# 190812-1a.net
KiCad netlist of a schematic drawn in EAGLE
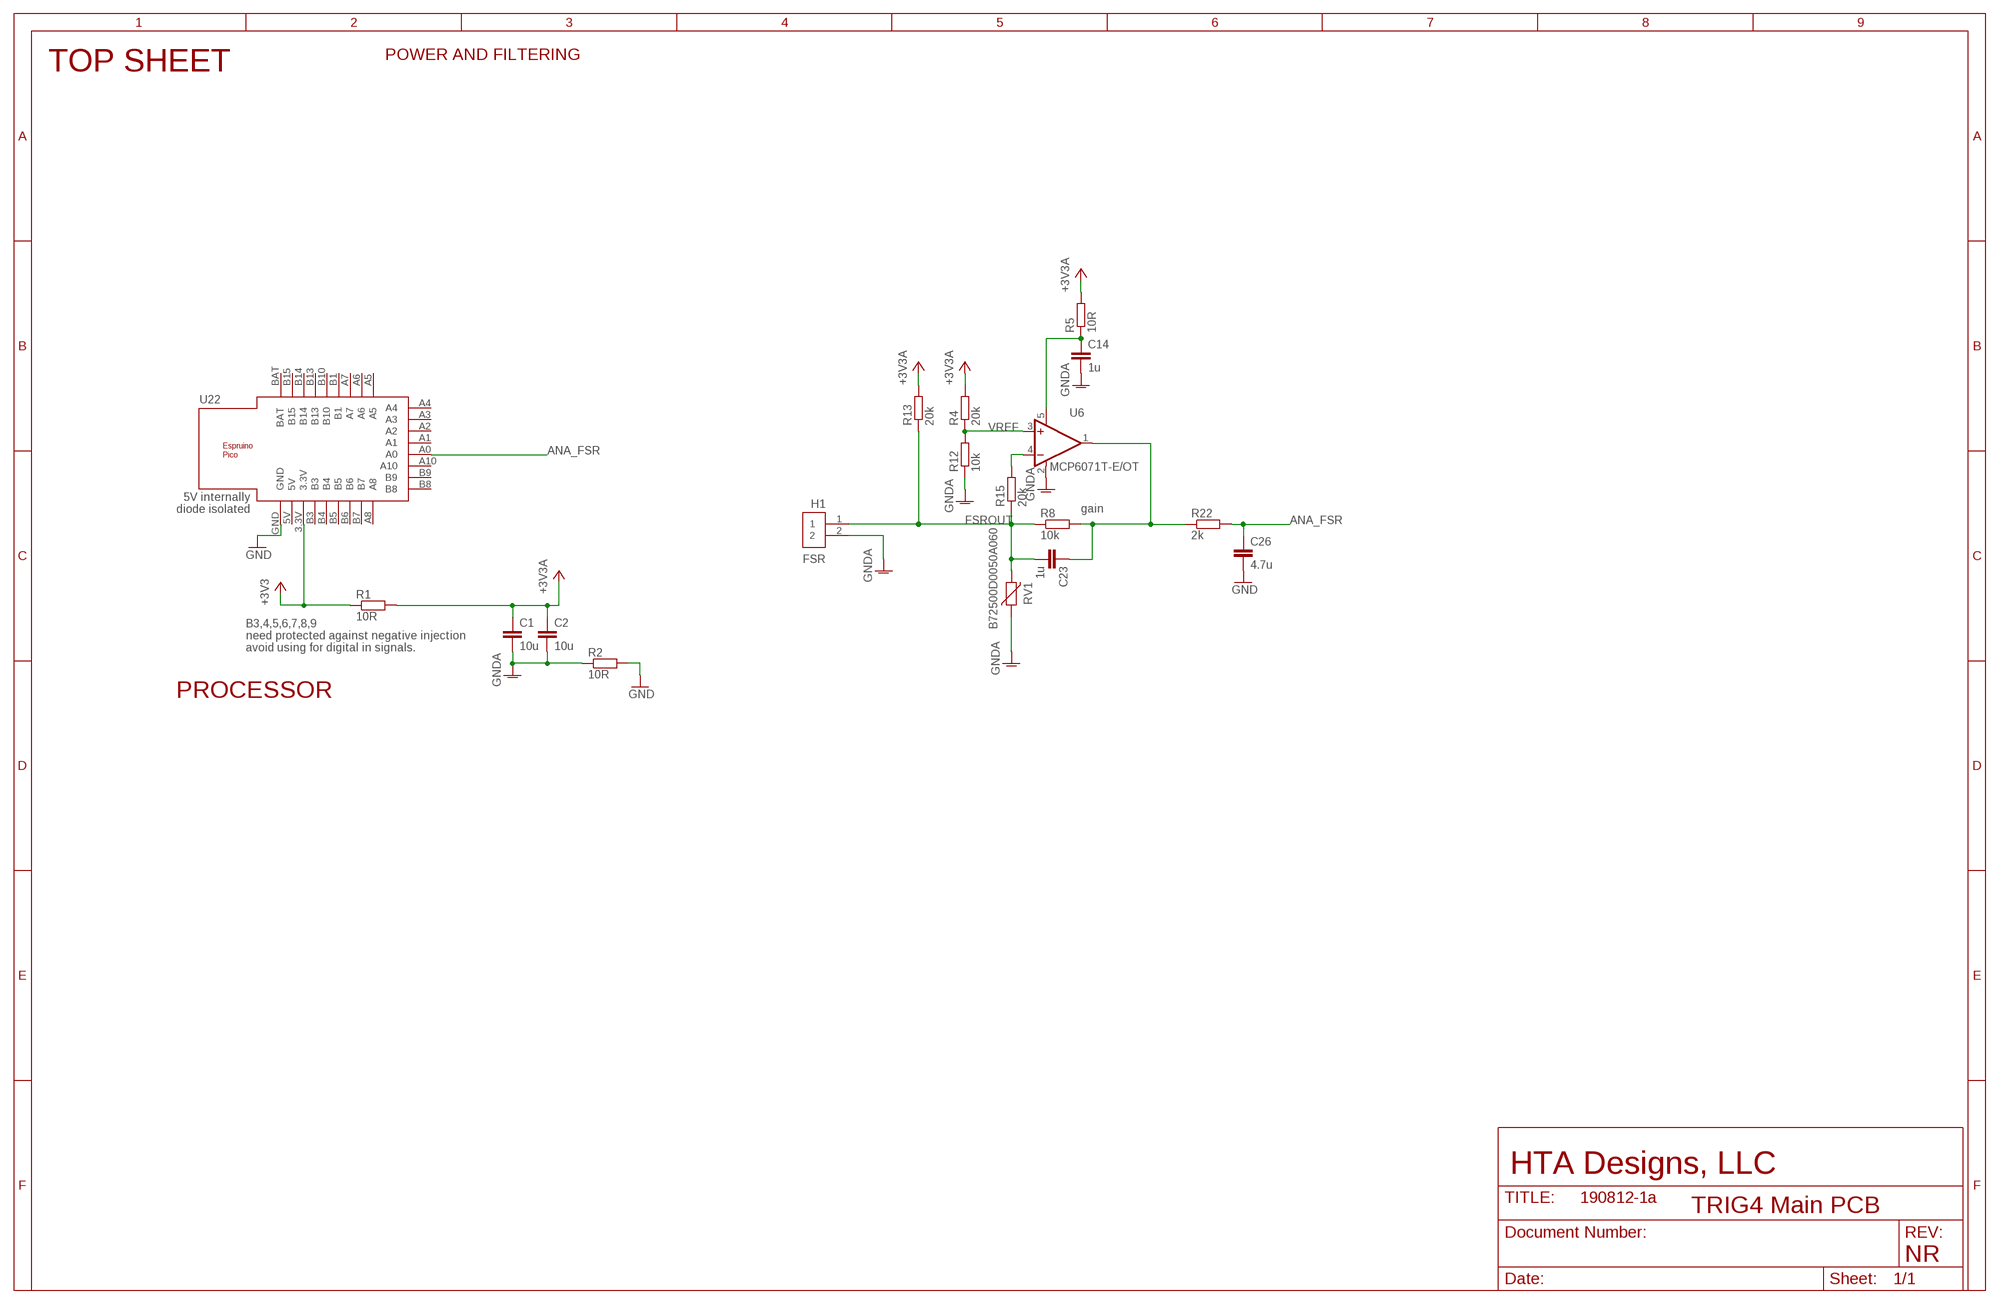
[diagram p0: schematic, sheet 1]

(export (version "E")
  (design (tool "Eeschema 10.0.6"))
  (components
    (comp (ref "C1")
      (value "10u")
      (footprint "eagle-import:C1206")
      (libsource (lib "eagle-import") (part "C-EUC1206"))
    )
    (comp (ref "C2")
      (value "10u")
      (footprint "eagle-import:C1206")
      (libsource (lib "eagle-import") (part "C-EUC1206"))
    )
    (comp (ref "C14")
      (value "1u")
      (footprint "eagle-import:C0603")
      (libsource (lib "eagle-import") (part "C-EUC0603"))
    )
    (comp (ref "C23")
      (value "1u")
      (footprint "eagle-import:C0805")
      (libsource (lib "eagle-import") (part "C-EUC0805"))
    )
    (comp (ref "C26")
      (value "4.7u")
      (footprint "eagle-import:C0805")
      (libsource (lib "eagle-import") (part "C-EUC0805"))
    )
    (comp (ref "H1")
      (value "FSR-CONNECTOR-RUGER")
      (footprint "eagle-import:1X02")
      (libsource (lib "eagle-import") (part "FSR-CONNECTOR-RUGER"))
    )
    (comp (ref "R1")
      (value "10R")
      (footprint "eagle-import:R0603")
      (libsource (lib "eagle-import") (part "R-EU_R0603"))
    )
    (comp (ref "R2")
      (value "10R")
      (footprint "eagle-import:R0603")
      (libsource (lib "eagle-import") (part "R-EU_R0603"))
    )
    (comp (ref "R4")
      (value "20k")
      (footprint "eagle-import:R0603")
      (libsource (lib "eagle-import") (part "R-EU_R0603"))
    )
    (comp (ref "R5")
      (value "10R")
      (footprint "eagle-import:R0603")
      (libsource (lib "eagle-import") (part "R-EU_R0603"))
    )
    (comp (ref "R8")
      (value "10k")
      (footprint "eagle-import:R0603")
      (libsource (lib "eagle-import") (part "R-EU_R0603"))
    )
    (comp (ref "R12")
      (value "10k")
      (footprint "eagle-import:R0603")
      (libsource (lib "eagle-import") (part "R-EU_R0603"))
    )
    (comp (ref "R13")
      (value "20k")
      (footprint "eagle-import:R0603")
      (libsource (lib "eagle-import") (part "R-EU_R0603"))
    )
    (comp (ref "R15")
      (value "20k")
      (footprint "eagle-import:R0603")
      (libsource (lib "eagle-import") (part "R-EU_R0603"))
    )
    (comp (ref "R22")
      (value "2k")
      (footprint "eagle-import:R0603")
      (libsource (lib "eagle-import") (part "R-EU_R0603"))
    )
    (comp (ref "RV1")
      (value "B72500D0050A060")
      (footprint "eagle-import:VARC1608X90")
      (libsource (lib "eagle-import") (part "B72500D0050A060"))
    )
    (comp (ref "U6")
      (value "MCP6071T-E/OT")
      (footprint "eagle-import:SOT95P270X145-5")
      (libsource (lib "eagle-import") (part "MCP6071T-E/OT"))
    )
    (comp (ref "U22")
      (value "ESPRUINO_PICO_SMDONLY")
      (footprint "eagle-import:ESPRUINO_PICO_SMDONLY")
      (libsource (lib "eagle-import") (part "ESPRUINO_PICO_SMDONLY"))
    )
  )
  (nets
    (net (code "1") (name "+3V3") (class "Default")
      (node (ref "R1") (pin "1") (pinfunction "1_1") (pintype "passive"))
      (node (ref "U22") (pin "3.3V") (pinfunction "3.3V_3.3V") (pintype "bidirectional"))
    )
    (net (code "2") (name "+3V3A") (class "Default")
      (node (ref "C1") (pin "1") (pinfunction "1_1") (pintype "passive"))
      (node (ref "C2") (pin "1") (pinfunction "1_1") (pintype "passive"))
      (node (ref "R1") (pin "2") (pinfunction "2_2") (pintype "passive"))
      (node (ref "R13") (pin "2") (pinfunction "2_2") (pintype "passive"))
      (node (ref "R4") (pin "2") (pinfunction "2_2") (pintype "passive"))
      (node (ref "R5") (pin "2") (pinfunction "2_2") (pintype "passive"))
    )
    (net (code "3") (name "/ANA_FSR") (class "Default")
      (node (ref "C26") (pin "1") (pinfunction "1_1") (pintype "passive"))
      (node (ref "R22") (pin "2") (pinfunction "2_2") (pintype "passive"))
      (node (ref "U22") (pin "A0") (pinfunction "A0_A0") (pintype "bidirectional"))
    )
    (net (code "4") (name "/FSROUT") (class "Default")
      (node (ref "C23") (pin "2") (pinfunction "2_2") (pintype "passive"))
      (node (ref "H1") (pin "1") (pinfunction "1_1") (pintype "passive"))
      (node (ref "R13") (pin "1") (pinfunction "1_1") (pintype "passive"))
      (node (ref "R15") (pin "1") (pinfunction "1_1") (pintype "passive"))
      (node (ref "R8") (pin "1") (pinfunction "1_1") (pintype "passive"))
      (node (ref "RV1") (pin "2") (pinfunction "2_2") (pintype "passive"))
    )
    (net (code "5") (name "/VREF") (class "Default")
      (node (ref "R12") (pin "2") (pinfunction "2_2") (pintype "passive"))
      (node (ref "R4") (pin "1") (pinfunction "1_1") (pintype "passive"))
      (node (ref "U6") (pin "3") (pinfunction "+IN_3") (pintype "input"))
    )
    (net (code "6") (name "GND") (class "Default")
      (node (ref "C26") (pin "2") (pinfunction "2_2") (pintype "passive"))
      (node (ref "R2") (pin "2") (pinfunction "2_2") (pintype "passive"))
      (node (ref "U22") (pin "GND") (pinfunction "GND_GND") (pintype "bidirectional"))
    )
    (net (code "7") (name "GNDA") (class "Default")
      (node (ref "C1") (pin "2") (pinfunction "2_2") (pintype "passive"))
      (node (ref "C14") (pin "2") (pinfunction "2_2") (pintype "passive"))
      (node (ref "C2") (pin "2") (pinfunction "2_2") (pintype "passive"))
      (node (ref "H1") (pin "2") (pinfunction "2_2") (pintype "passive"))
      (node (ref "R12") (pin "1") (pinfunction "1_1") (pintype "passive"))
      (node (ref "R2") (pin "1") (pinfunction "1_1") (pintype "passive"))
      (node (ref "RV1") (pin "1") (pinfunction "1_1") (pintype "passive"))
      (node (ref "U6") (pin "2") (pinfunction "V-_2") (pintype "power_in"))
    )
    (net (code "8") (name "Net-(U6--IN)") (class "Default")
      (node (ref "R15") (pin "2") (pinfunction "2_2") (pintype "passive"))
      (node (ref "U6") (pin "4") (pinfunction "-IN_4") (pintype "input"))
    )
    (net (code "9") (name "Net-(U6-OUT)") (class "Default")
      (node (ref "C23") (pin "1") (pinfunction "1_1") (pintype "passive"))
      (node (ref "R22") (pin "1") (pinfunction "1_1") (pintype "passive"))
      (node (ref "R8") (pin "2") (pinfunction "2_2") (pintype "passive"))
      (node (ref "U6") (pin "1") (pinfunction "OUT_1") (pintype "output"))
    )
    (net (code "10") (name "Net-(U6-V+)") (class "Default")
      (node (ref "C14") (pin "1") (pinfunction "1_1") (pintype "passive"))
      (node (ref "R5") (pin "1") (pinfunction "1_1") (pintype "passive"))
      (node (ref "U6") (pin "5") (pinfunction "V+_5") (pintype "power_in"))
    )
    (net (code "11") (name "unconnected-(U22-Pad5V)") (class "Default")
      (node (ref "U22") (pin "5V") (pinfunction "5V_5V") (pintype "bidirectional"))
    )
    (net (code "12") (name "unconnected-(U22-PadA1)") (class "Default")
      (node (ref "U22") (pin "A1") (pinfunction "A1_A1") (pintype "bidirectional"))
    )
    (net (code "13") (name "unconnected-(U22-PadA2)") (class "Default")
      (node (ref "U22") (pin "A2") (pinfunction "A2_A2") (pintype "bidirectional"))
    )
    (net (code "14") (name "unconnected-(U22-PadA3)") (class "Default")
      (node (ref "U22") (pin "A3") (pinfunction "A3_A3") (pintype "bidirectional"))
    )
    (net (code "15") (name "unconnected-(U22-PadA4)") (class "Default")
      (node (ref "U22") (pin "A4") (pinfunction "A4_A4") (pintype "bidirectional"))
    )
    (net (code "16") (name "unconnected-(U22-PadA5)") (class "Default")
      (node (ref "U22") (pin "A5") (pinfunction "A5_A5") (pintype "bidirectional"))
    )
    (net (code "17") (name "unconnected-(U22-PadA6)") (class "Default")
      (node (ref "U22") (pin "A6") (pinfunction "A6_A6") (pintype "bidirectional"))
    )
    (net (code "18") (name "unconnected-(U22-PadA7)") (class "Default")
      (node (ref "U22") (pin "A7") (pinfunction "A7_A7") (pintype "bidirectional"))
    )
    (net (code "19") (name "unconnected-(U22-PadA8)") (class "Default")
      (node (ref "U22") (pin "A8") (pinfunction "A8_A8") (pintype "bidirectional"))
    )
    (net (code "20") (name "unconnected-(U22-PadA10)") (class "Default")
      (node (ref "U22") (pin "A10") (pinfunction "A10_A10") (pintype "bidirectional"))
    )
    (net (code "21") (name "unconnected-(U22-PadB1)") (class "Default")
      (node (ref "U22") (pin "B1") (pinfunction "B1_B1") (pintype "bidirectional"))
    )
    (net (code "22") (name "unconnected-(U22-PadB3)") (class "Default")
      (node (ref "U22") (pin "B3") (pinfunction "B3_B3") (pintype "bidirectional"))
    )
    (net (code "23") (name "unconnected-(U22-PadB4)") (class "Default")
      (node (ref "U22") (pin "B4") (pinfunction "B4_B4") (pintype "bidirectional"))
    )
    (net (code "24") (name "unconnected-(U22-PadB5)") (class "Default")
      (node (ref "U22") (pin "B5") (pinfunction "B5_B5") (pintype "bidirectional"))
    )
    (net (code "25") (name "unconnected-(U22-PadB6)") (class "Default")
      (node (ref "U22") (pin "B6") (pinfunction "B6_B6") (pintype "bidirectional"))
    )
    (net (code "26") (name "unconnected-(U22-PadB7)") (class "Default")
      (node (ref "U22") (pin "B7") (pinfunction "B7_B7") (pintype "bidirectional"))
    )
    (net (code "27") (name "unconnected-(U22-PadB8)") (class "Default")
      (node (ref "U22") (pin "B8") (pinfunction "B8_B8") (pintype "bidirectional"))
    )
    (net (code "28") (name "unconnected-(U22-PadB9)") (class "Default")
      (node (ref "U22") (pin "B9") (pinfunction "B9_B9") (pintype "bidirectional"))
    )
    (net (code "29") (name "unconnected-(U22-PadB10)") (class "Default")
      (node (ref "U22") (pin "B10") (pinfunction "B10_B10") (pintype "bidirectional"))
    )
    (net (code "30") (name "unconnected-(U22-PadB13)") (class "Default")
      (node (ref "U22") (pin "B13") (pinfunction "B13_B13") (pintype "bidirectional"))
    )
    (net (code "31") (name "unconnected-(U22-PadB14)") (class "Default")
      (node (ref "U22") (pin "B14") (pinfunction "B14_B14") (pintype "bidirectional"))
    )
    (net (code "32") (name "unconnected-(U22-PadB15)") (class "Default")
      (node (ref "U22") (pin "B15") (pinfunction "B15_B15") (pintype "bidirectional"))
    )
    (net (code "33") (name "unconnected-(U22-PadBAT)") (class "Default")
      (node (ref "U22") (pin "BAT") (pinfunction "BAT_BAT") (pintype "bidirectional"))
    )
  )
)
